# HSADCircuit.net
KiCad netlist of a schematic drawn in Altium Designer
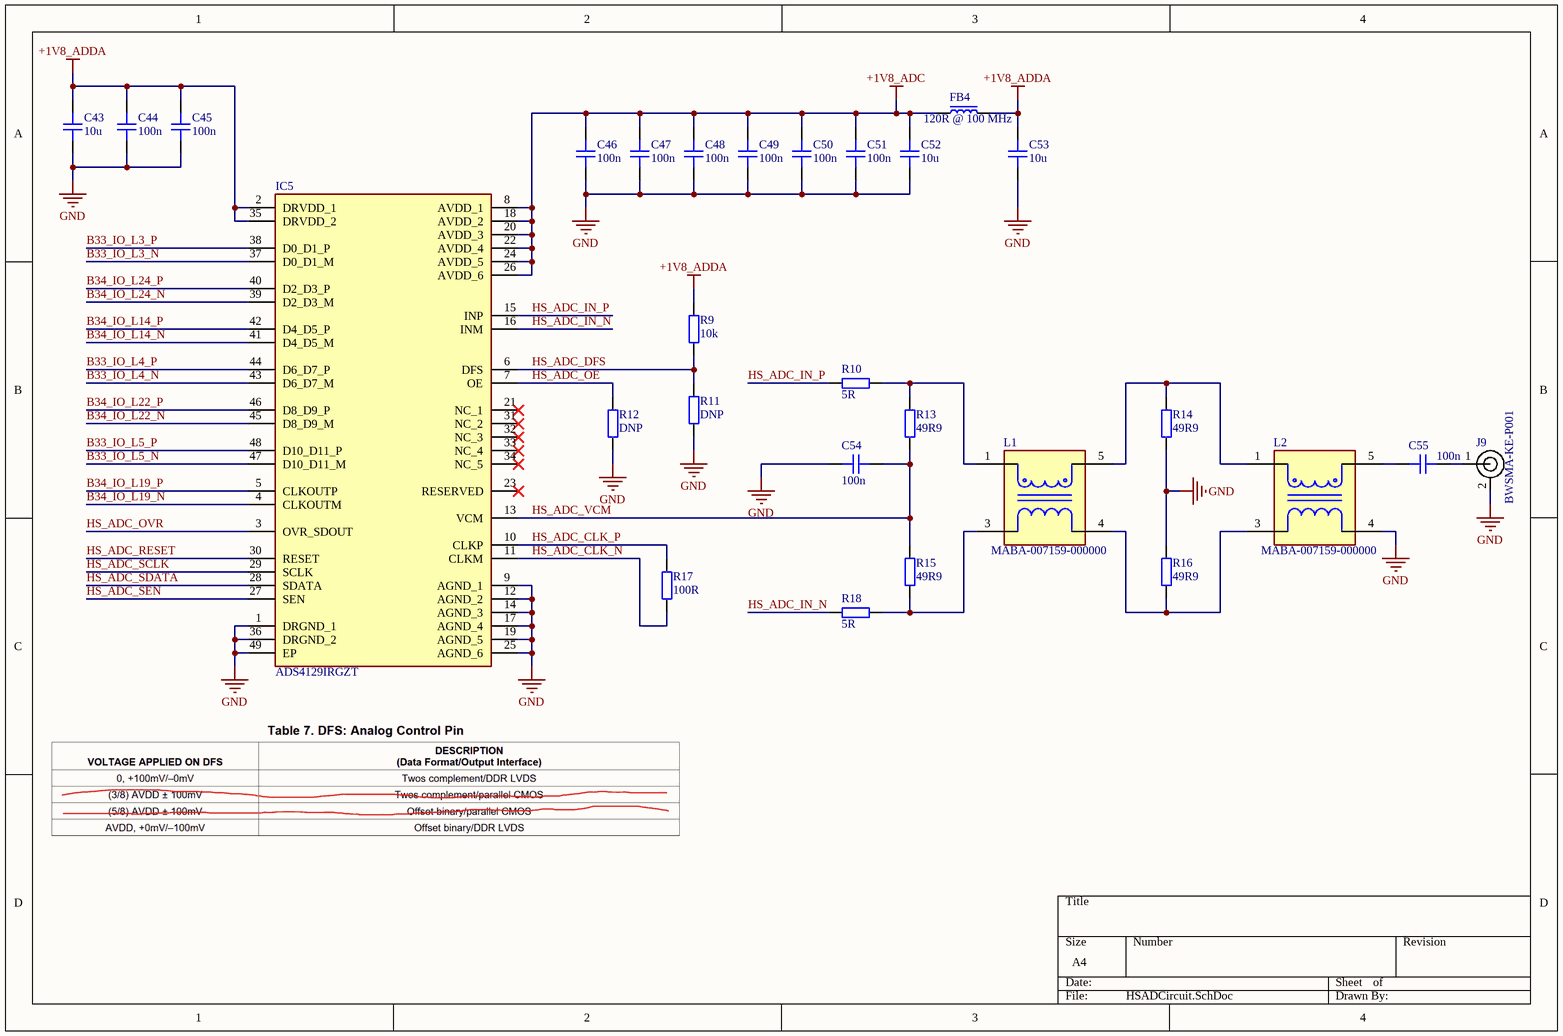
[diagram p0: HSADCircuit.SchDoc]

(export (version "E")
  (design (tool "Eeschema 10.0.6"))
  (components
    (comp (ref "C43")
      (value "10u")
      (footprint "CAP_0603")
      (description "Capacitor SMD 0603")
      (libsource (lib "Schematic-Lib-PhilsLab") (part "CAP_0603"))
    )
    (comp (ref "C44")
      (value "100n")
      (footprint "CAP_0402")
      (description "Capacitor SMD 0402")
      (libsource (lib "Schematic-Lib-PhilsLab") (part "CAP_0402"))
    )
    (comp (ref "C45")
      (value "100n")
      (footprint "CAP_0402")
      (description "Capacitor SMD 0402")
      (libsource (lib "Schematic-Lib-PhilsLab") (part "CAP_0402"))
    )
    (comp (ref "C46")
      (value "100n")
      (footprint "CAP_0402")
      (description "Capacitor SMD 0402")
      (libsource (lib "Schematic-Lib-PhilsLab") (part "CAP_0402"))
    )
    (comp (ref "C47")
      (value "100n")
      (footprint "CAP_0402")
      (description "Capacitor SMD 0402")
      (libsource (lib "Schematic-Lib-PhilsLab") (part "CAP_0402"))
    )
    (comp (ref "C48")
      (value "100n")
      (footprint "CAP_0402")
      (description "Capacitor SMD 0402")
      (libsource (lib "Schematic-Lib-PhilsLab") (part "CAP_0402"))
    )
    (comp (ref "C49")
      (value "100n")
      (footprint "CAP_0402")
      (description "Capacitor SMD 0402")
      (libsource (lib "Schematic-Lib-PhilsLab") (part "CAP_0402"))
    )
    (comp (ref "C50")
      (value "100n")
      (footprint "CAP_0402")
      (description "Capacitor SMD 0402")
      (libsource (lib "Schematic-Lib-PhilsLab") (part "CAP_0402"))
    )
    (comp (ref "C51")
      (value "100n")
      (footprint "CAP_0402")
      (description "Capacitor SMD 0402")
      (libsource (lib "Schematic-Lib-PhilsLab") (part "CAP_0402"))
    )
    (comp (ref "C52")
      (value "10u")
      (footprint "CAP_0603")
      (description "Capacitor SMD 0603")
      (libsource (lib "Schematic-Lib-PhilsLab") (part "CAP_0603"))
    )
    (comp (ref "C53")
      (value "10u")
      (footprint "CAP_0603")
      (description "Capacitor SMD 0603")
      (libsource (lib "Schematic-Lib-PhilsLab") (part "CAP_0603"))
    )
    (comp (ref "C54")
      (value "100n")
      (footprint "CAP_0402")
      (description "Capacitor SMD 0402")
      (libsource (lib "Schematic-Lib-PhilsLab") (part "CAP_0402"))
    )
    (comp (ref "C55")
      (value "100n")
      (footprint "CAP_0402")
      (description "Capacitor SMD 0402")
      (libsource (lib "Schematic-Lib-PhilsLab") (part "CAP_0402"))
    )
    (comp (ref "FB4")
      (value "120R @ 100 MHz")
      (footprint "FB_0603")
      (description "Ferrite Bead SMD 0603")
      (libsource (lib "Schematic-Lib-PhilsLab") (part "FB_0603"))
    )
    (comp (ref "IC5")
      (value "ADS4129IRGZT")
      (footprint "JetsonTx2_PCBLib:QFN50P700X700X100-49N-D")
      (description "Integrated Circuit")
      (fields (field (name "MOUSER PART NUMBER") "595-ADS4129IRGZT"))
      (libsource (lib "JetsonTx2_SCHLib") (part "ADS4129IRGZT"))
    )
    (comp (ref "J9")
      (value "BWSMA-KE-P001")
      (footprint "BWSMA-KE-P001")
      (libsource (lib "JetsonTx2_SCHLib") (part "BWSMA-KE-P001"))
    )
    (comp (ref "L1")
      (value "MABA-007159-000000")
      (footprint "FP-MABA-007159-000000-MFG")
      (description "BALUN 4.5MHZ-3GHZ 1:1 6SMD FLAT")
      (libsource (lib "JetsonTx2_SCHLib") (part "MABA-007159-000000"))
    )
    (comp (ref "L2")
      (value "MABA-007159-000000")
      (footprint "FP-MABA-007159-000000-MFG")
      (description "BALUN 4.5MHZ-3GHZ 1:1 6SMD FLAT")
      (libsource (lib "JetsonTx2_SCHLib") (part "MABA-007159-000000"))
    )
    (comp (ref "R9")
      (value "10k")
      (footprint "RES_0402")
      (description "Resistor SMD 0402")
      (libsource (lib "Schematic-Lib-PhilsLab") (part "RES_0402"))
    )
    (comp (ref "R10")
      (value "5R")
      (footprint "RES_0402")
      (description "Resistor SMD 0402")
      (libsource (lib "Schematic-Lib-PhilsLab") (part "RES_0402"))
    )
    (comp (ref "R11")
      (value "DNP")
      (footprint "RES_0402")
      (description "Resistor SMD 0402")
      (libsource (lib "Schematic-Lib-PhilsLab") (part "RES_0402"))
    )
    (comp (ref "R12")
      (value "DNP")
      (footprint "RES_0402")
      (description "Resistor SMD 0402")
      (libsource (lib "Schematic-Lib-PhilsLab") (part "RES_0402"))
    )
    (comp (ref "R13")
      (value "49R9")
      (footprint "RES_0402")
      (description "Resistor SMD 0402")
      (libsource (lib "Schematic-Lib-PhilsLab") (part "RES_0402"))
    )
    (comp (ref "R14")
      (value "49R9")
      (footprint "RES_0402")
      (description "Resistor SMD 0402")
      (libsource (lib "Schematic-Lib-PhilsLab") (part "RES_0402"))
    )
    (comp (ref "R15")
      (value "49R9")
      (footprint "RES_0402")
      (description "Resistor SMD 0402")
      (libsource (lib "Schematic-Lib-PhilsLab") (part "RES_0402"))
    )
    (comp (ref "R16")
      (value "49R9")
      (footprint "RES_0402")
      (description "Resistor SMD 0402")
      (libsource (lib "Schematic-Lib-PhilsLab") (part "RES_0402"))
    )
    (comp (ref "R17")
      (value "100R")
      (footprint "RES_0402")
      (description "Resistor SMD 0402")
      (libsource (lib "Schematic-Lib-PhilsLab") (part "RES_0402"))
    )
    (comp (ref "R18")
      (value "5R")
      (footprint "RES_0402")
      (description "Resistor SMD 0402")
      (libsource (lib "Schematic-Lib-PhilsLab") (part "RES_0402"))
    )
  )
  (nets
    (net (code "1") (name "+1V8_ADC") (class "Default")
      (node (ref "C46") (pin "1") (pinfunction "1_1") (pintype "passive"))
      (node (ref "C47") (pin "1") (pinfunction "1_1") (pintype "passive"))
      (node (ref "C48") (pin "1") (pinfunction "1_1") (pintype "passive"))
      (node (ref "C49") (pin "1") (pinfunction "1_1") (pintype "passive"))
      (node (ref "C50") (pin "1") (pinfunction "1_1") (pintype "passive"))
      (node (ref "C51") (pin "1") (pinfunction "1_1") (pintype "passive"))
      (node (ref "C52") (pin "2") (pinfunction "2_2") (pintype "passive"))
      (node (ref "FB4") (pin "1") (pinfunction "1_1") (pintype "passive"))
      (node (ref "IC5") (pin "18") (pinfunction "AVDD_2_18") (pintype "passive"))
      (node (ref "IC5") (pin "20") (pinfunction "AVDD_3_20") (pintype "passive"))
      (node (ref "IC5") (pin "22") (pinfunction "AVDD_4_22") (pintype "passive"))
      (node (ref "IC5") (pin "24") (pinfunction "AVDD_5_24") (pintype "passive"))
      (node (ref "IC5") (pin "26") (pinfunction "AVDD_6_26") (pintype "passive"))
      (node (ref "IC5") (pin "8") (pinfunction "AVDD_1_8") (pintype "passive"))
    )
    (net (code "2") (name "+1V8_ADDA") (class "Default")
      (node (ref "C43") (pin "2") (pinfunction "2_2") (pintype "passive"))
      (node (ref "C44") (pin "1") (pinfunction "1_1") (pintype "passive"))
      (node (ref "C45") (pin "1") (pinfunction "1_1") (pintype "passive"))
      (node (ref "C53") (pin "2") (pinfunction "2_2") (pintype "passive"))
      (node (ref "FB4") (pin "2") (pinfunction "2_2") (pintype "passive"))
      (node (ref "IC5") (pin "2") (pinfunction "DRVDD_1_2") (pintype "passive"))
      (node (ref "IC5") (pin "35") (pinfunction "DRVDD_2_35") (pintype "passive"))
      (node (ref "R9") (pin "2") (pinfunction "2_2") (pintype "passive"))
    )
    (net (code "3") (name "/B33_IO_L3_N") (class "Default")
      (node (ref "IC5") (pin "37") (pinfunction "D0_D1_M_37") (pintype "passive"))
    )
    (net (code "4") (name "/B33_IO_L3_P") (class "Default")
      (node (ref "IC5") (pin "38") (pinfunction "D0_D1_P_38") (pintype "passive"))
    )
    (net (code "5") (name "/B33_IO_L4_N") (class "Default")
      (node (ref "IC5") (pin "43") (pinfunction "D6_D7_M_43") (pintype "passive"))
    )
    (net (code "6") (name "/B33_IO_L4_P") (class "Default")
      (node (ref "IC5") (pin "44") (pinfunction "D6_D7_P_44") (pintype "passive"))
    )
    (net (code "7") (name "/B33_IO_L5_N") (class "Default")
      (node (ref "IC5") (pin "47") (pinfunction "D10_D11_M_47") (pintype "passive"))
    )
    (net (code "8") (name "/B33_IO_L5_P") (class "Default")
      (node (ref "IC5") (pin "48") (pinfunction "D10_D11_P_48") (pintype "passive"))
    )
    (net (code "9") (name "/B34_IO_L14_N") (class "Default")
      (node (ref "IC5") (pin "41") (pinfunction "D4_D5_M_41") (pintype "passive"))
    )
    (net (code "10") (name "/B34_IO_L14_P") (class "Default")
      (node (ref "IC5") (pin "42") (pinfunction "D4_D5_P_42") (pintype "passive"))
    )
    (net (code "11") (name "/B34_IO_L19_N") (class "Default")
      (node (ref "IC5") (pin "4") (pinfunction "CLKOUTM_4") (pintype "passive"))
    )
    (net (code "12") (name "/B34_IO_L19_P") (class "Default")
      (node (ref "IC5") (pin "5") (pinfunction "CLKOUTP_5") (pintype "passive"))
    )
    (net (code "13") (name "/B34_IO_L22_N") (class "Default")
      (node (ref "IC5") (pin "45") (pinfunction "D8_D9_M_45") (pintype "passive"))
    )
    (net (code "14") (name "/B34_IO_L22_P") (class "Default")
      (node (ref "IC5") (pin "46") (pinfunction "D8_D9_P_46") (pintype "passive"))
    )
    (net (code "15") (name "/B34_IO_L24_N") (class "Default")
      (node (ref "IC5") (pin "39") (pinfunction "D2_D3_M_39") (pintype "passive"))
    )
    (net (code "16") (name "/B34_IO_L24_P") (class "Default")
      (node (ref "IC5") (pin "40") (pinfunction "D2_D3_P_40") (pintype "passive"))
    )
    (net (code "17") (name "/HS_ADC_CLK_N") (class "Default")
      (node (ref "IC5") (pin "11") (pinfunction "CLKM_11") (pintype "passive"))
      (node (ref "R17") (pin "1") (pinfunction "1_1") (pintype "passive"))
    )
    (net (code "18") (name "/HS_ADC_CLK_P") (class "Default")
      (node (ref "IC5") (pin "10") (pinfunction "CLKP_10") (pintype "passive"))
      (node (ref "R17") (pin "2") (pinfunction "2_2") (pintype "passive"))
    )
    (net (code "19") (name "/HS_ADC_DFS") (class "Default")
      (node (ref "IC5") (pin "6") (pinfunction "DFS_6") (pintype "passive"))
      (node (ref "R11") (pin "2") (pinfunction "2_2") (pintype "passive"))
      (node (ref "R9") (pin "1") (pinfunction "1_1") (pintype "passive"))
    )
    (net (code "20") (name "/HS_ADC_IN_N") (class "Default")
      (node (ref "IC5") (pin "16") (pinfunction "INM_16") (pintype "passive"))
      (node (ref "R18") (pin "2") (pinfunction "2_2") (pintype "passive"))
    )
    (net (code "21") (name "/HS_ADC_IN_P") (class "Default")
      (node (ref "IC5") (pin "15") (pinfunction "INP_15") (pintype "passive"))
      (node (ref "R10") (pin "2") (pinfunction "2_2") (pintype "passive"))
    )
    (net (code "22") (name "/HS_ADC_OE") (class "Default")
      (node (ref "IC5") (pin "7") (pinfunction "OE_7") (pintype "passive"))
      (node (ref "R12") (pin "2") (pinfunction "2_2") (pintype "passive"))
    )
    (net (code "23") (name "/HS_ADC_OVR") (class "Default")
      (node (ref "IC5") (pin "3") (pinfunction "OVR_SDOUT_3") (pintype "passive"))
    )
    (net (code "24") (name "/HS_ADC_RESET") (class "Default")
      (node (ref "IC5") (pin "30") (pinfunction "RESET_30") (pintype "passive"))
    )
    (net (code "25") (name "/HS_ADC_SCLK") (class "Default")
      (node (ref "IC5") (pin "29") (pinfunction "SCLK_29") (pintype "passive"))
    )
    (net (code "26") (name "/HS_ADC_SDATA") (class "Default")
      (node (ref "IC5") (pin "28") (pinfunction "SDATA_28") (pintype "passive"))
    )
    (net (code "27") (name "/HS_ADC_SEN") (class "Default")
      (node (ref "IC5") (pin "27") (pinfunction "SEN_27") (pintype "passive"))
    )
    (net (code "28") (name "/HS_ADC_VCM") (class "Default")
      (node (ref "C54") (pin "1") (pinfunction "1_1") (pintype "passive"))
      (node (ref "IC5") (pin "13") (pinfunction "VCM_13") (pintype "passive"))
      (node (ref "R13") (pin "2") (pinfunction "2_2") (pintype "passive"))
      (node (ref "R15") (pin "1") (pinfunction "1_1") (pintype "passive"))
    )
    (net (code "29") (name "GND") (class "Default")
      (node (ref "C43") (pin "1") (pinfunction "1_1") (pintype "passive"))
      (node (ref "C44") (pin "2") (pinfunction "2_2") (pintype "passive"))
      (node (ref "C45") (pin "2") (pinfunction "2_2") (pintype "passive"))
      (node (ref "C46") (pin "2") (pinfunction "2_2") (pintype "passive"))
      (node (ref "C47") (pin "2") (pinfunction "2_2") (pintype "passive"))
      (node (ref "C48") (pin "2") (pinfunction "2_2") (pintype "passive"))
      (node (ref "C49") (pin "2") (pinfunction "2_2") (pintype "passive"))
      (node (ref "C50") (pin "2") (pinfunction "2_2") (pintype "passive"))
      (node (ref "C51") (pin "2") (pinfunction "2_2") (pintype "passive"))
      (node (ref "C52") (pin "1") (pinfunction "1_1") (pintype "passive"))
      (node (ref "C53") (pin "1") (pinfunction "1_1") (pintype "passive"))
      (node (ref "C54") (pin "2") (pinfunction "2_2") (pintype "passive"))
      (node (ref "IC5") (pin "1") (pinfunction "DRGND_1_1") (pintype "passive"))
      (node (ref "IC5") (pin "12") (pinfunction "AGND_2_12") (pintype "passive"))
      (node (ref "IC5") (pin "14") (pinfunction "AGND_3_14") (pintype "passive"))
      (node (ref "IC5") (pin "17") (pinfunction "AGND_4_17") (pintype "passive"))
      (node (ref "IC5") (pin "19") (pinfunction "AGND_5_19") (pintype "passive"))
      (node (ref "IC5") (pin "25") (pinfunction "AGND_6_25") (pintype "passive"))
      (node (ref "IC5") (pin "36") (pinfunction "DRGND_2_36") (pintype "passive"))
      (node (ref "IC5") (pin "49") (pinfunction "EP_49") (pintype "passive"))
      (node (ref "IC5") (pin "9") (pinfunction "AGND_1_9") (pintype "passive"))
      (node (ref "J9") (pin "2") (pinfunction "2_2") (pintype "passive"))
      (node (ref "L2") (pin "4") (pinfunction "Primary_4") (pintype "passive"))
      (node (ref "R11") (pin "1") (pinfunction "1_1") (pintype "passive"))
      (node (ref "R12") (pin "1") (pinfunction "1_1") (pintype "passive"))
      (node (ref "R14") (pin "2") (pinfunction "2_2") (pintype "passive"))
      (node (ref "R16") (pin "1") (pinfunction "1_1") (pintype "passive"))
    )
    (net (code "30") (name "Net-(C55-Pad2)") (class "Default")
      (node (ref "C55") (pin "2") (pinfunction "2_2") (pintype "passive"))
      (node (ref "J9") (pin "1") (pinfunction "1_1") (pintype "passive"))
    )
    (net (code "31") (name "Net-(L1-Primary)") (class "Default")
      (node (ref "L1") (pin "4") (pinfunction "Primary_4") (pintype "passive"))
      (node (ref "L2") (pin "3") (pinfunction "Secondary_3") (pintype "passive"))
      (node (ref "R16") (pin "2") (pinfunction "2_2") (pintype "passive"))
    )
    (net (code "32") (name "Net-(L1-Primary_Dot)") (class "Default")
      (node (ref "L1") (pin "5") (pinfunction "Primary_Dot_5") (pintype "passive"))
      (node (ref "L2") (pin "1") (pinfunction "Secondary_Dot_1") (pintype "passive"))
      (node (ref "R14") (pin "1") (pinfunction "1_1") (pintype "passive"))
    )
    (net (code "33") (name "Net-(L1-Secondary)") (class "Default")
      (node (ref "L1") (pin "3") (pinfunction "Secondary_3") (pintype "passive"))
      (node (ref "R15") (pin "2") (pinfunction "2_2") (pintype "passive"))
      (node (ref "R18") (pin "1") (pinfunction "1_1") (pintype "passive"))
    )
    (net (code "34") (name "Net-(L1-Secondary_Dot)") (class "Default")
      (node (ref "L1") (pin "1") (pinfunction "Secondary_Dot_1") (pintype "passive"))
      (node (ref "R10") (pin "1") (pinfunction "1_1") (pintype "passive"))
      (node (ref "R13") (pin "1") (pinfunction "1_1") (pintype "passive"))
    )
    (net (code "35") (name "Net-(L2-Primary_Dot)") (class "Default")
      (node (ref "C55") (pin "1") (pinfunction "1_1") (pintype "passive"))
      (node (ref "L2") (pin "5") (pinfunction "Primary_Dot_5") (pintype "passive"))
    )
    (net (code "36") (name "unconnected-(IC5-NC_1-Pad21)") (class "Default")
      (node (ref "IC5") (pin "21") (pinfunction "NC_1_21") (pintype "passive+no_connect"))
    )
    (net (code "37") (name "unconnected-(IC5-NC_2-Pad31)") (class "Default")
      (node (ref "IC5") (pin "31") (pinfunction "NC_2_31") (pintype "passive+no_connect"))
    )
    (net (code "38") (name "unconnected-(IC5-NC_3-Pad32)") (class "Default")
      (node (ref "IC5") (pin "32") (pinfunction "NC_3_32") (pintype "passive+no_connect"))
    )
    (net (code "39") (name "unconnected-(IC5-NC_4-Pad33)") (class "Default")
      (node (ref "IC5") (pin "33") (pinfunction "NC_4_33") (pintype "passive+no_connect"))
    )
    (net (code "40") (name "unconnected-(IC5-NC_5-Pad34)") (class "Default")
      (node (ref "IC5") (pin "34") (pinfunction "NC_5_34") (pintype "passive+no_connect"))
    )
    (net (code "41") (name "unconnected-(IC5-RESERVED-Pad23)") (class "Default")
      (node (ref "IC5") (pin "23") (pinfunction "RESERVED_23") (pintype "passive+no_connect"))
    )
  )
)
